# RoboClaw_V2_Board.net
KiCad netlist of a schematic drawn in EAGLE
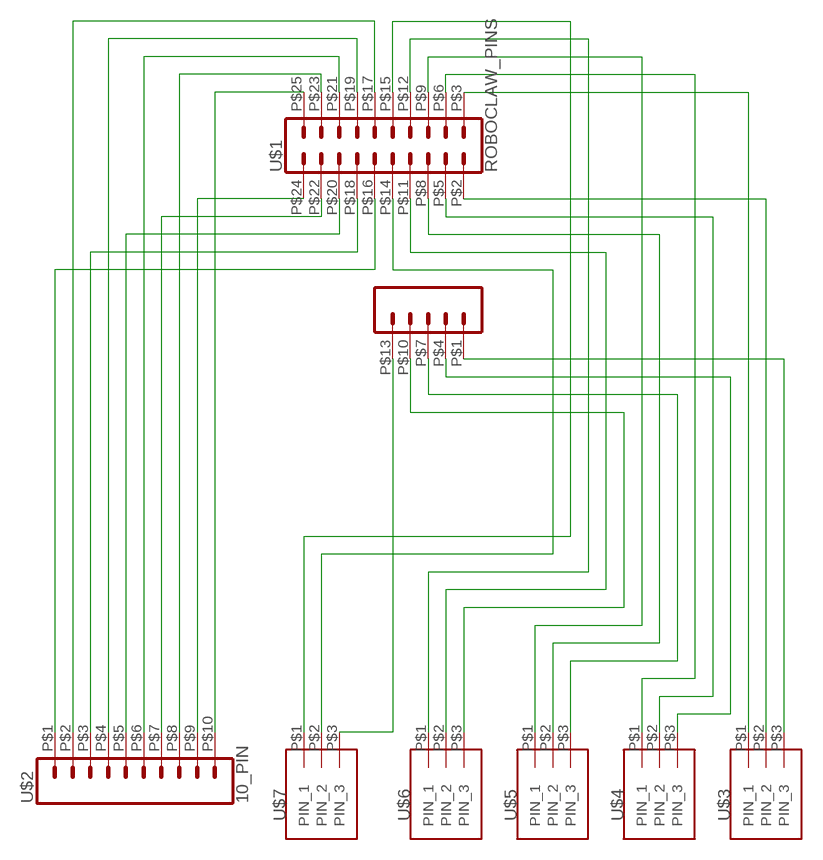
[diagram p0: schematic, sheet 1]

(export (version "E")
  (design (tool "Eeschema 10.0.6"))
  (components
    (comp (ref "U$1")
      (value "ROBOCLAW_PINS")
      (footprint "eagle-import:ROBOCLAW_PINS")
      (libsource (lib "eagle-import") (part "ROBOCLAW_PINS"))
    )
    (comp (ref "U$2")
      (value "10_PIN")
      (footprint "eagle-import:10_PIN")
      (libsource (lib "eagle-import") (part "10_PIN"))
    )
    (comp (ref "U$3")
      (value "3_PIN")
      (footprint "eagle-import:3_PIN")
      (libsource (lib "eagle-import") (part "3_PIN"))
    )
    (comp (ref "U$4")
      (value "3_PIN")
      (footprint "eagle-import:3_PIN")
      (libsource (lib "eagle-import") (part "3_PIN"))
    )
    (comp (ref "U$5")
      (value "3_PIN")
      (footprint "eagle-import:3_PIN")
      (libsource (lib "eagle-import") (part "3_PIN"))
    )
    (comp (ref "U$6")
      (value "3_PIN")
      (footprint "eagle-import:3_PIN")
      (libsource (lib "eagle-import") (part "3_PIN"))
    )
    (comp (ref "U$7")
      (value "3_PIN")
      (footprint "eagle-import:3_PIN")
      (libsource (lib "eagle-import") (part "3_PIN"))
    )
  )
  (nets
    (net (code "1") (name "Net-(U$1-PIN_1)") (class "Default")
      (node (ref "U$1") (pin "P$1") (pinfunction "PIN_1_P$1") (pintype "passive"))
      (node (ref "U$3") (pin "P$3") (pinfunction "PIN_3_P$3") (pintype "bidirectional"))
    )
    (net (code "2") (name "Net-(U$1-PIN_2)") (class "Default")
      (node (ref "U$1") (pin "P$2") (pinfunction "PIN_2_P$2") (pintype "passive"))
      (node (ref "U$3") (pin "P$2") (pinfunction "PIN_2_P$2") (pintype "bidirectional"))
    )
    (net (code "3") (name "Net-(U$1-PIN_3)") (class "Default")
      (node (ref "U$1") (pin "P$3") (pinfunction "PIN_3_P$3") (pintype "passive"))
      (node (ref "U$3") (pin "P$1") (pinfunction "PIN_1_P$1") (pintype "bidirectional"))
    )
    (net (code "4") (name "Net-(U$1-PIN_4)") (class "Default")
      (node (ref "U$1") (pin "P$4") (pinfunction "PIN_4_P$4") (pintype "passive"))
      (node (ref "U$4") (pin "P$3") (pinfunction "PIN_3_P$3") (pintype "bidirectional"))
    )
    (net (code "5") (name "Net-(U$1-PIN_5)") (class "Default")
      (node (ref "U$1") (pin "P$5") (pinfunction "PIN_5_P$5") (pintype "passive"))
      (node (ref "U$4") (pin "P$2") (pinfunction "PIN_2_P$2") (pintype "bidirectional"))
    )
    (net (code "6") (name "Net-(U$1-PIN_6)") (class "Default")
      (node (ref "U$1") (pin "P$6") (pinfunction "PIN_6_P$6") (pintype "passive"))
      (node (ref "U$4") (pin "P$1") (pinfunction "PIN_1_P$1") (pintype "bidirectional"))
    )
    (net (code "7") (name "Net-(U$1-PIN_7)") (class "Default")
      (node (ref "U$1") (pin "P$7") (pinfunction "PIN_7_P$7") (pintype "passive"))
      (node (ref "U$5") (pin "P$3") (pinfunction "PIN_3_P$3") (pintype "bidirectional"))
    )
    (net (code "8") (name "Net-(U$1-PIN_8)") (class "Default")
      (node (ref "U$1") (pin "P$8") (pinfunction "PIN_8_P$8") (pintype "passive"))
      (node (ref "U$5") (pin "P$2") (pinfunction "PIN_2_P$2") (pintype "bidirectional"))
    )
    (net (code "9") (name "Net-(U$1-PIN_9)") (class "Default")
      (node (ref "U$1") (pin "P$9") (pinfunction "PIN_9_P$9") (pintype "passive"))
      (node (ref "U$5") (pin "P$1") (pinfunction "PIN_1_P$1") (pintype "bidirectional"))
    )
    (net (code "10") (name "Net-(U$1-PIN_10)") (class "Default")
      (node (ref "U$1") (pin "P$10") (pinfunction "PIN_10_P$10") (pintype "passive"))
      (node (ref "U$6") (pin "P$3") (pinfunction "PIN_3_P$3") (pintype "bidirectional"))
    )
    (net (code "11") (name "Net-(U$1-PIN_11)") (class "Default")
      (node (ref "U$1") (pin "P$11") (pinfunction "PIN_11_P$11") (pintype "passive"))
      (node (ref "U$6") (pin "P$2") (pinfunction "PIN_2_P$2") (pintype "bidirectional"))
    )
    (net (code "12") (name "Net-(U$1-PIN_12)") (class "Default")
      (node (ref "U$1") (pin "P$12") (pinfunction "PIN_12_P$12") (pintype "passive"))
      (node (ref "U$6") (pin "P$1") (pinfunction "PIN_1_P$1") (pintype "bidirectional"))
    )
    (net (code "13") (name "Net-(U$1-PIN_13)") (class "Default")
      (node (ref "U$1") (pin "P$13") (pinfunction "PIN_13_P$13") (pintype "passive"))
      (node (ref "U$7") (pin "P$3") (pinfunction "PIN_3_P$3") (pintype "bidirectional"))
    )
    (net (code "14") (name "Net-(U$1-PIN_14)") (class "Default")
      (node (ref "U$1") (pin "P$14") (pinfunction "PIN_14_P$14") (pintype "passive"))
      (node (ref "U$7") (pin "P$2") (pinfunction "PIN_2_P$2") (pintype "bidirectional"))
    )
    (net (code "15") (name "Net-(U$1-PIN_15)") (class "Default")
      (node (ref "U$1") (pin "P$15") (pinfunction "PIN_15_P$15") (pintype "passive"))
      (node (ref "U$7") (pin "P$1") (pinfunction "PIN_1_P$1") (pintype "bidirectional"))
    )
    (net (code "16") (name "Net-(U$1-PIN_16)") (class "Default")
      (node (ref "U$1") (pin "P$16") (pinfunction "PIN_16_P$16") (pintype "passive"))
      (node (ref "U$2") (pin "P$1") (pinfunction "PIN_1_P$1") (pintype "passive"))
    )
    (net (code "17") (name "Net-(U$1-PIN_17)") (class "Default")
      (node (ref "U$1") (pin "P$17") (pinfunction "PIN_17_P$17") (pintype "passive"))
      (node (ref "U$2") (pin "P$2") (pinfunction "PIN_2_P$2") (pintype "passive"))
    )
    (net (code "18") (name "Net-(U$1-PIN_18)") (class "Default")
      (node (ref "U$1") (pin "P$18") (pinfunction "PIN_18_P$18") (pintype "passive"))
      (node (ref "U$2") (pin "P$3") (pinfunction "PIN_3_P$3") (pintype "passive"))
    )
    (net (code "19") (name "Net-(U$1-PIN_19)") (class "Default")
      (node (ref "U$1") (pin "P$19") (pinfunction "PIN_19_P$19") (pintype "passive"))
      (node (ref "U$2") (pin "P$4") (pinfunction "PIN_4_P$4") (pintype "passive"))
    )
    (net (code "20") (name "Net-(U$1-PIN_20)") (class "Default")
      (node (ref "U$1") (pin "P$20") (pinfunction "PIN_20_P$20") (pintype "passive"))
      (node (ref "U$2") (pin "P$5") (pinfunction "PIN_5_P$5") (pintype "passive"))
    )
    (net (code "21") (name "Net-(U$1-PIN_21)") (class "Default")
      (node (ref "U$1") (pin "P$21") (pinfunction "PIN_21_P$21") (pintype "passive"))
      (node (ref "U$2") (pin "P$6") (pinfunction "PIN_6_P$6") (pintype "passive"))
    )
    (net (code "22") (name "Net-(U$1-PIN_22)") (class "Default")
      (node (ref "U$1") (pin "P$22") (pinfunction "PIN_22_P$22") (pintype "passive"))
      (node (ref "U$2") (pin "P$7") (pinfunction "PIN_7_P$7") (pintype "passive"))
    )
    (net (code "23") (name "Net-(U$1-PIN_23)") (class "Default")
      (node (ref "U$1") (pin "P$23") (pinfunction "PIN_23_P$23") (pintype "passive"))
      (node (ref "U$2") (pin "P$8") (pinfunction "PIN_8_P$8") (pintype "passive"))
    )
    (net (code "24") (name "Net-(U$1-PIN_24)") (class "Default")
      (node (ref "U$1") (pin "P$24") (pinfunction "PIN_24_P$24") (pintype "passive"))
      (node (ref "U$2") (pin "P$9") (pinfunction "PIN_9_P$9") (pintype "passive"))
    )
    (net (code "25") (name "Net-(U$1-PIN_25)") (class "Default")
      (node (ref "U$1") (pin "P$25") (pinfunction "PIN_25_P$25") (pintype "passive"))
      (node (ref "U$2") (pin "P$10") (pinfunction "PIN_10_P$10") (pintype "passive"))
    )
  )
)
